# ledControlpcb.net
KiCad netlist of a schematic drawn in EAGLE
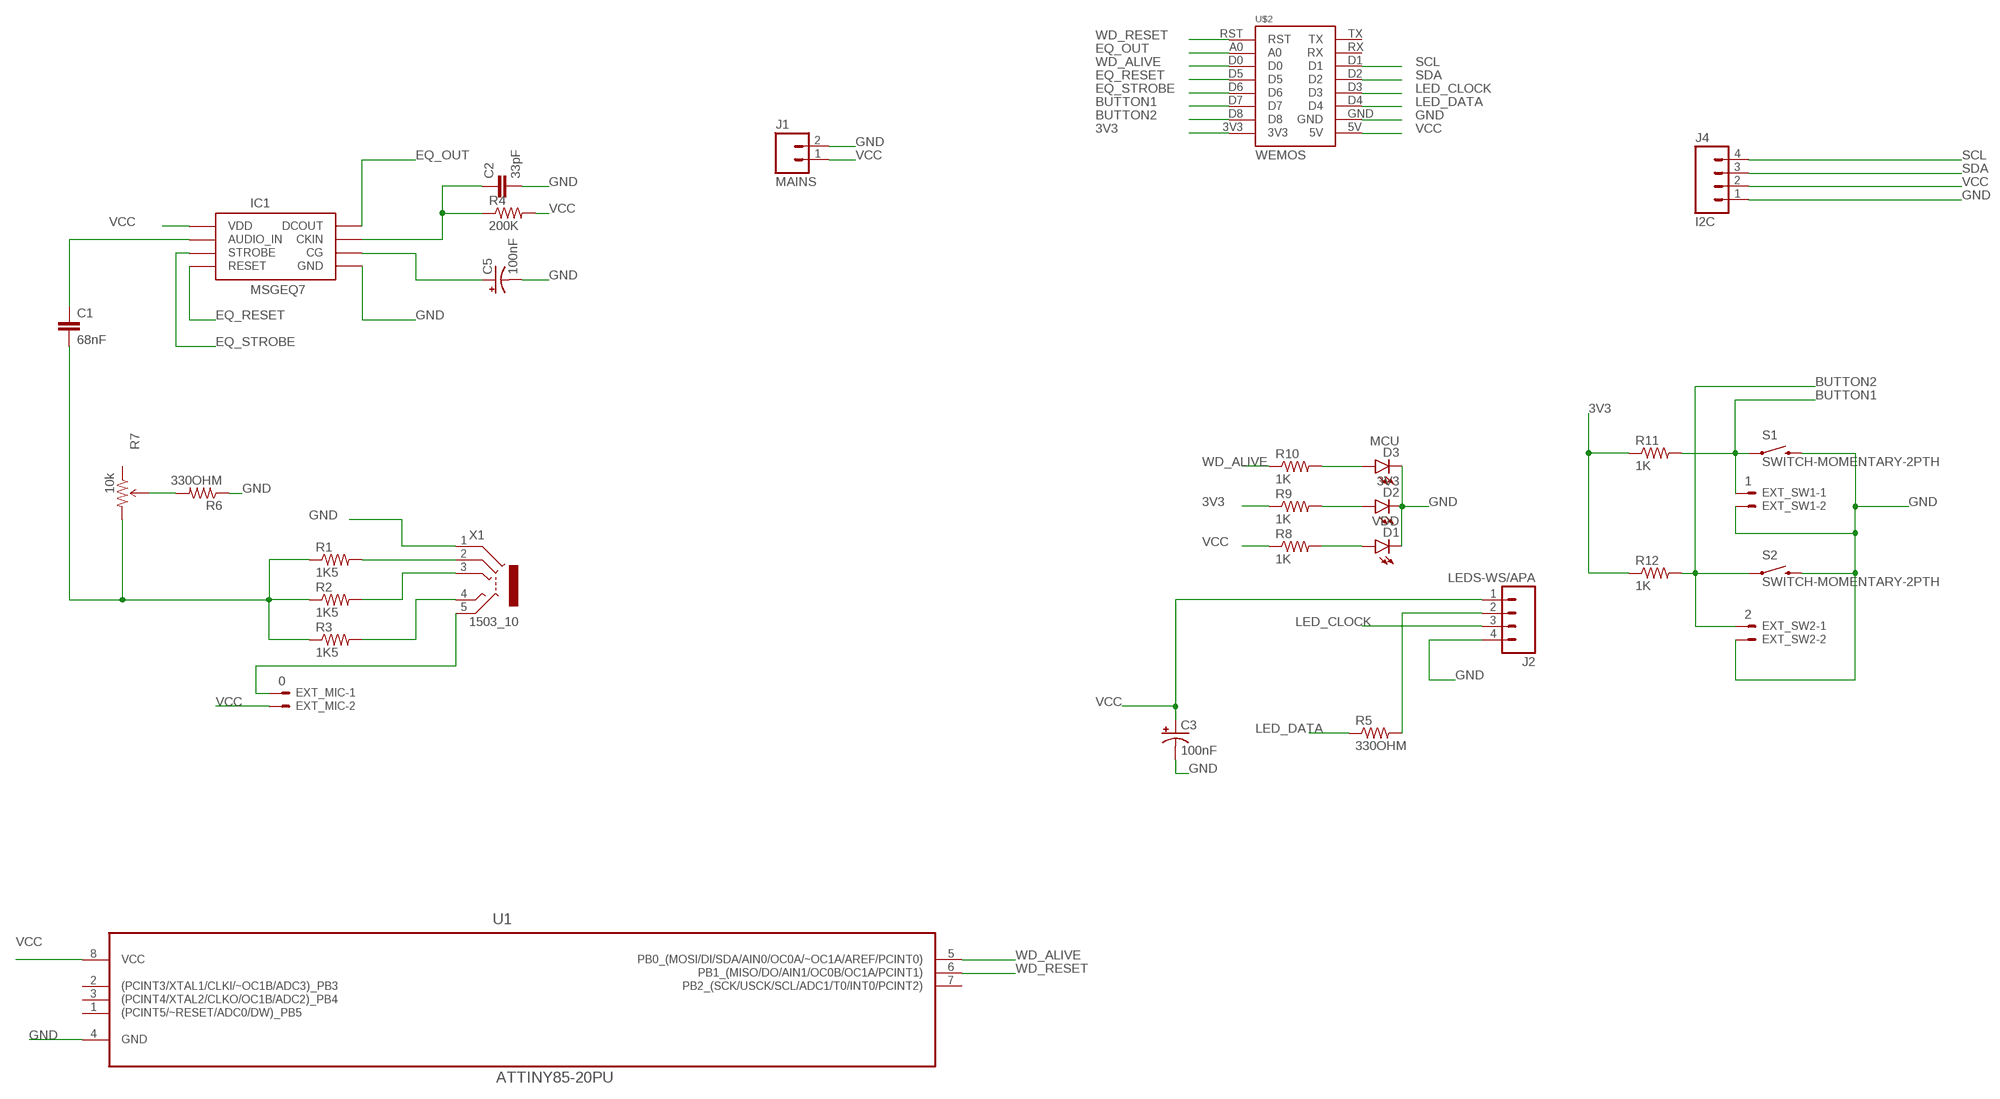
[diagram p0: schematic, sheet 1]

(export (version "E")
  (design (tool "Eeschema 10.0.6"))
  (components
    (comp (ref "C1")
      (value "68nF")
      (footprint "eagle-import:0603-CAP")
      (libsource (lib "eagle-import") (part "CAP0603-CAP"))
    )
    (comp (ref "C2")
      (value "33pF")
      (footprint "eagle-import:0603-CAP")
      (libsource (lib "eagle-import") (part "CAP0603-CAP"))
    )
    (comp (ref "C3")
      (value "100nF")
      (footprint "eagle-import:EIA3216")
      (libsource (lib "eagle-import") (part "CAP_POL1206"))
    )
    (comp (ref "C5")
      (value "100nF")
      (footprint "eagle-import:EIA3216")
      (libsource (lib "eagle-import") (part "CAP_POL1206"))
    )
    (comp (ref "D1")
      (value "VDD")
      (footprint "eagle-import:LED-0603")
      (libsource (lib "eagle-import") (part "LED0603"))
    )
    (comp (ref "D2")
      (value "3V3")
      (footprint "eagle-import:LED-0603")
      (libsource (lib "eagle-import") (part "LED0603"))
    )
    (comp (ref "D3")
      (value "MCU")
      (footprint "eagle-import:LED-0603")
      (libsource (lib "eagle-import") (part "LED0603"))
    )
    (comp (ref "EXT_MIC")
      (value "0")
      (footprint "eagle-import:22-23-2021")
      (fields (field (name "MF") "MOLEX") (field (name "MPN") "22-23-2021"))
      (libsource (lib "eagle-import") (part "22-23-2021"))
    )
    (comp (ref "EXT_SW1")
      (value "1")
      (footprint "eagle-import:22-23-2021")
      (fields (field (name "MF") "MOLEX") (field (name "MPN") "22-23-2021"))
      (libsource (lib "eagle-import") (part "22-23-2021"))
    )
    (comp (ref "EXT_SW2")
      (value "2")
      (footprint "eagle-import:22-23-2021")
      (fields (field (name "MF") "MOLEX") (field (name "MPN") "22-23-2021"))
      (libsource (lib "eagle-import") (part "22-23-2021"))
    )
    (comp (ref "IC1")
      (value "MSGEQ7DIP")
      (footprint "eagle-import:DIL08")
      (libsource (lib "eagle-import") (part "MSGEQ7DIP"))
    )
    (comp (ref "J1")
      (value "MAINS")
      (footprint "eagle-import:MOLEX-1X2")
      (libsource (lib "eagle-import") (part "M02POLAR"))
    )
    (comp (ref "J2")
      (value "LEDS-WS/APA")
      (footprint "eagle-import:MOLEX-1X4")
      (libsource (lib "eagle-import") (part "M04POLAR"))
    )
    (comp (ref "J4")
      (value "I2C")
      (footprint "eagle-import:MOLEX-1X4")
      (libsource (lib "eagle-import") (part "M04POLAR"))
    )
    (comp (ref "R1")
      (value "1K5")
      (footprint "eagle-import:0603-RES")
      (libsource (lib "eagle-import") (part "RESISTOR0603"))
    )
    (comp (ref "R2")
      (value "1K5")
      (footprint "eagle-import:0603-RES")
      (libsource (lib "eagle-import") (part "RESISTOR0603"))
    )
    (comp (ref "R3")
      (value "1K5")
      (footprint "eagle-import:0603-RES")
      (libsource (lib "eagle-import") (part "RESISTOR0603-RES"))
    )
    (comp (ref "R4")
      (value "200K")
      (footprint "eagle-import:0603-RES")
      (libsource (lib "eagle-import") (part "RESISTOR0603"))
    )
    (comp (ref "R5")
      (value "330OHM")
      (footprint "eagle-import:0603-RES")
      (libsource (lib "eagle-import") (part "RESISTOR0603"))
    )
    (comp (ref "R6")
      (value "330OHM")
      (footprint "eagle-import:0603-RES")
      (libsource (lib "eagle-import") (part "RESISTOR0603-RES"))
    )
    (comp (ref "R7")
      (value "10k")
      (footprint "eagle-import:TRIM_POT_PTH")
      (libsource (lib "eagle-import") (part "TRIMPOTPTH"))
    )
    (comp (ref "R8")
      (value "1K")
      (footprint "eagle-import:0603-RES")
      (libsource (lib "eagle-import") (part "RESISTOR0603"))
    )
    (comp (ref "R9")
      (value "1K")
      (footprint "eagle-import:0603-RES")
      (libsource (lib "eagle-import") (part "RESISTOR0603"))
    )
    (comp (ref "R10")
      (value "1K")
      (footprint "eagle-import:0603-RES")
      (libsource (lib "eagle-import") (part "RESISTOR0603"))
    )
    (comp (ref "R11")
      (value "1K")
      (footprint "eagle-import:0603-RES")
      (libsource (lib "eagle-import") (part "RESISTOR0603"))
    )
    (comp (ref "R12")
      (value "1K")
      (footprint "eagle-import:0603-RES")
      (libsource (lib "eagle-import") (part "RESISTOR0603"))
    )
    (comp (ref "S1")
      (value "SWITCH-MOMENTARY-2PTH")
      (footprint "eagle-import:TACTILE-PTH")
      (libsource (lib "eagle-import") (part "SWITCH-MOMENTARY-2PTH"))
    )
    (comp (ref "S2")
      (value "SWITCH-MOMENTARY-2PTH")
      (footprint "eagle-import:TACTILE-PTH")
      (libsource (lib "eagle-import") (part "SWITCH-MOMENTARY-2PTH"))
    )
    (comp (ref "U$2")
      (value "WEMOS")
      (footprint "eagle-import:WEMOS")
      (libsource (lib "eagle-import") (part "WEMOS"))
    )
    (comp (ref "U1")
      (value "ATTINY85-20PU")
      (footprint "eagle-import:DIP254P762X533-8")
      (libsource (lib "eagle-import") (part "ATTINY85-20PU"))
    )
    (comp (ref "X1")
      (value "1503_10")
      (footprint "eagle-import:1503_10")
      (libsource (lib "eagle-import") (part "1503_10"))
    )
  )
  (nets
    (net (code "1") (name "/3V3") (class "Default")
      (node (ref "R11") (pin "1") (pinfunction "1_1") (pintype "passive"))
      (node (ref "R12") (pin "1") (pinfunction "1_1") (pintype "passive"))
      (node (ref "R9") (pin "1") (pinfunction "1_1") (pintype "passive"))
      (node (ref "U$2") (pin "3V3") (pinfunction "3V3_3V3") (pintype "bidirectional"))
    )
    (net (code "2") (name "/BUTTON1") (class "Default")
      (node (ref "EXT_SW1") (pin "1") (pinfunction "S_1") (pintype "passive"))
      (node (ref "R11") (pin "2") (pinfunction "2_2") (pintype "passive"))
      (node (ref "S1") (pin "1") (pinfunction "1_1") (pintype "passive"))
      (node (ref "U$2") (pin "D7") (pinfunction "D7_D7") (pintype "bidirectional"))
    )
    (net (code "3") (name "/BUTTON2") (class "Default")
      (node (ref "EXT_SW2") (pin "1") (pinfunction "S_1") (pintype "passive"))
      (node (ref "R12") (pin "2") (pinfunction "2_2") (pintype "passive"))
      (node (ref "S2") (pin "1") (pinfunction "1_1") (pintype "passive"))
      (node (ref "U$2") (pin "D8") (pinfunction "D8_D8") (pintype "bidirectional"))
    )
    (net (code "4") (name "/EQ_OUT") (class "Default")
      (node (ref "IC1") (pin "3") (pinfunction "DCOUT_3") (pintype "bidirectional"))
      (node (ref "U$2") (pin "A0") (pinfunction "A0_A0") (pintype "bidirectional"))
    )
    (net (code "5") (name "/EQ_RESET") (class "Default")
      (node (ref "IC1") (pin "7") (pinfunction "RESET_7") (pintype "input"))
      (node (ref "U$2") (pin "D5") (pinfunction "D5_D5") (pintype "bidirectional"))
    )
    (net (code "6") (name "/EQ_STROBE") (class "Default")
      (node (ref "IC1") (pin "4") (pinfunction "STROBE_4") (pintype "input"))
      (node (ref "U$2") (pin "D6") (pinfunction "D6_D6") (pintype "bidirectional"))
    )
    (net (code "7") (name "/GND") (class "Default")
      (node (ref "C2") (pin "2") (pinfunction "2_2") (pintype "passive"))
      (node (ref "C3") (pin "C") (pinfunction "-_C") (pintype "passive"))
      (node (ref "C5") (pin "C") (pinfunction "-_C") (pintype "passive"))
      (node (ref "D1") (pin "C") (pinfunction "C_C") (pintype "passive"))
      (node (ref "D2") (pin "C") (pinfunction "C_C") (pintype "passive"))
      (node (ref "D3") (pin "C") (pinfunction "C_C") (pintype "passive"))
      (node (ref "EXT_SW1") (pin "2") (pinfunction "S_2") (pintype "passive"))
      (node (ref "EXT_SW2") (pin "2") (pinfunction "S_2") (pintype "passive"))
      (node (ref "IC1") (pin "2") (pinfunction "GND_2") (pintype "bidirectional"))
      (node (ref "J1") (pin "2") (pinfunction "2_2") (pintype "passive"))
      (node (ref "J2") (pin "4") (pinfunction "4_4") (pintype "passive"))
      (node (ref "J4") (pin "1") (pinfunction "1_1") (pintype "passive"))
      (node (ref "R6") (pin "1") (pinfunction "1_1") (pintype "passive"))
      (node (ref "S1") (pin "3") (pinfunction "2_3") (pintype "passive"))
      (node (ref "S2") (pin "3") (pinfunction "2_3") (pintype "passive"))
      (node (ref "U$2") (pin "GND") (pinfunction "GND_GND") (pintype "bidirectional"))
      (node (ref "U1") (pin "4") (pinfunction "GND_4") (pintype "passive"))
      (node (ref "X1") (pin "1") (pinfunction "1_1") (pintype "passive"))
    )
    (net (code "8") (name "/LED_CLOCK") (class "Default")
      (node (ref "J2") (pin "3") (pinfunction "3_3") (pintype "passive"))
      (node (ref "U$2") (pin "D3") (pinfunction "D3_D3") (pintype "bidirectional"))
    )
    (net (code "9") (name "/LED_DATA") (class "Default")
      (node (ref "R5") (pin "1") (pinfunction "1_1") (pintype "passive"))
      (node (ref "U$2") (pin "D4") (pinfunction "D4_D4") (pintype "bidirectional"))
    )
    (net (code "10") (name "/SCL") (class "Default")
      (node (ref "J4") (pin "4") (pinfunction "4_4") (pintype "passive"))
      (node (ref "U$2") (pin "D1") (pinfunction "D1_D1") (pintype "bidirectional"))
    )
    (net (code "11") (name "/SDA") (class "Default")
      (node (ref "J4") (pin "3") (pinfunction "3_3") (pintype "passive"))
      (node (ref "U$2") (pin "D2") (pinfunction "D2_D2") (pintype "bidirectional"))
    )
    (net (code "12") (name "/VCC") (class "Default")
      (node (ref "C3") (pin "A") (pinfunction "+_A") (pintype "passive"))
      (node (ref "EXT_MIC") (pin "2") (pinfunction "S_2") (pintype "passive"))
      (node (ref "IC1") (pin "1") (pinfunction "VDD_1") (pintype "input"))
      (node (ref "J1") (pin "1") (pinfunction "1_1") (pintype "passive"))
      (node (ref "J2") (pin "1") (pinfunction "1_1") (pintype "passive"))
      (node (ref "J4") (pin "2") (pinfunction "2_2") (pintype "passive"))
      (node (ref "R4") (pin "2") (pinfunction "2_2") (pintype "passive"))
      (node (ref "R8") (pin "1") (pinfunction "1_1") (pintype "passive"))
      (node (ref "U$2") (pin "5V") (pinfunction "5V_5V") (pintype "bidirectional"))
      (node (ref "U1") (pin "8") (pinfunction "VCC_8") (pintype "power_in"))
    )
    (net (code "13") (name "/WD_ALIVE") (class "Default")
      (node (ref "R10") (pin "1") (pinfunction "1_1") (pintype "passive"))
      (node (ref "U$2") (pin "D0") (pinfunction "D0_D0") (pintype "bidirectional"))
      (node (ref "U1") (pin "5") (pinfunction "PB0_(MOSI/DI/SDA/AIN0/OC0A/~{OC1A/AREF/PCINT0})_5") (pintype "bidirectional"))
    )
    (net (code "14") (name "/WD_RESET") (class "Default")
      (node (ref "U$2") (pin "RST") (pinfunction "RST_RST") (pintype "bidirectional"))
      (node (ref "U1") (pin "6") (pinfunction "PB1_(MISO/DO/AIN1/OC0B/OC1A/PCINT1)_6") (pintype "bidirectional"))
    )
    (net (code "15") (name "Net-(C5-+)") (class "Default")
      (node (ref "C5") (pin "A") (pinfunction "+_A") (pintype "passive"))
      (node (ref "IC1") (pin "6") (pinfunction "CG_6") (pintype "bidirectional"))
    )
    (net (code "16") (name "Net-(D1-PadA)") (class "Default")
      (node (ref "D1") (pin "A") (pinfunction "A_A") (pintype "passive"))
      (node (ref "R8") (pin "2") (pinfunction "2_2") (pintype "passive"))
    )
    (net (code "17") (name "Net-(D2-PadA)") (class "Default")
      (node (ref "D2") (pin "A") (pinfunction "A_A") (pintype "passive"))
      (node (ref "R9") (pin "2") (pinfunction "2_2") (pintype "passive"))
    )
    (net (code "18") (name "Net-(D3-PadA)") (class "Default")
      (node (ref "D3") (pin "A") (pinfunction "A_A") (pintype "passive"))
      (node (ref "R10") (pin "2") (pinfunction "2_2") (pintype "passive"))
    )
    (net (code "19") (name "Net-(EXT_MICA-S)") (class "Default")
      (node (ref "EXT_MIC") (pin "1") (pinfunction "S_1") (pintype "passive"))
      (node (ref "X1") (pin "5") (pinfunction "5_5") (pintype "passive"))
    )
    (net (code "20") (name "Net-(IC1-AUDIO_IN)") (class "Default")
      (node (ref "C1") (pin "1") (pinfunction "1_1") (pintype "passive"))
      (node (ref "IC1") (pin "5") (pinfunction "AUDIO_IN_5") (pintype "input"))
    )
    (net (code "21") (name "Net-(IC1-CKIN)") (class "Default")
      (node (ref "C2") (pin "1") (pinfunction "1_1") (pintype "passive"))
      (node (ref "IC1") (pin "8") (pinfunction "CKIN_8") (pintype "bidirectional"))
      (node (ref "R4") (pin "1") (pinfunction "1_1") (pintype "passive"))
    )
    (net (code "22") (name "Net-(J2-Pad2)") (class "Default")
      (node (ref "J2") (pin "2") (pinfunction "2_2") (pintype "passive"))
      (node (ref "R5") (pin "2") (pinfunction "2_2") (pintype "passive"))
    )
    (net (code "23") (name "Net-(R1-Pad2)") (class "Default")
      (node (ref "R1") (pin "2") (pinfunction "2_2") (pintype "passive"))
      (node (ref "X1") (pin "2") (pinfunction "2_2") (pintype "passive"))
    )
    (net (code "24") (name "Net-(R2-Pad2)") (class "Default")
      (node (ref "R2") (pin "2") (pinfunction "2_2") (pintype "passive"))
      (node (ref "X1") (pin "3") (pinfunction "3_3") (pintype "passive"))
    )
    (net (code "25") (name "Net-(R3-Pad2)") (class "Default")
      (node (ref "R3") (pin "2") (pinfunction "2_2") (pintype "passive"))
      (node (ref "X1") (pin "4") (pinfunction "4_4") (pintype "passive"))
    )
    (net (code "26") (name "Net-(R7-CW)") (class "Default")
      (node (ref "C1") (pin "2") (pinfunction "2_2") (pintype "passive"))
      (node (ref "R1") (pin "1") (pinfunction "1_1") (pintype "passive"))
      (node (ref "R2") (pin "1") (pinfunction "1_1") (pintype "passive"))
      (node (ref "R3") (pin "1") (pinfunction "1_1") (pintype "passive"))
      (node (ref "R7") (pin "3") (pinfunction "CW_3") (pintype "passive"))
    )
    (net (code "27") (name "Net-(R7-WIPER)") (class "Default")
      (node (ref "R6") (pin "2") (pinfunction "2_2") (pintype "passive"))
      (node (ref "R7") (pin "2") (pinfunction "WIPER_2") (pintype "passive"))
    )
    (net (code "28") (name "unconnected-(R7-CCW-Pad1)") (class "Default")
      (node (ref "R7") (pin "1") (pinfunction "CCW_1") (pintype "passive"))
    )
    (net (code "29") (name "unconnected-(U$2-PadRX)") (class "Default")
      (node (ref "U$2") (pin "RX") (pinfunction "RX_RX") (pintype "bidirectional"))
    )
    (net (code "30") (name "unconnected-(U$2-PadTX)") (class "Default")
      (node (ref "U$2") (pin "TX") (pinfunction "TX_TX") (pintype "bidirectional"))
    )
    (net (code "31") (name "unconnected-(U1-(PCINT3{slash}XTAL1{slash}CLKI{slash}~{OC1B{slash}ADC3})_PB3-Pad2)") (class "Default")
      (node (ref "U1") (pin "2") (pinfunction "(PCINT3/XTAL1/CLKI/~{OC1B/ADC3})_PB3_2") (pintype "bidirectional"))
    )
    (net (code "32") (name "unconnected-(U1-(PCINT4{slash}XTAL2{slash}CLKO{slash}OC1B{slash}ADC2)_PB4-Pad3)") (class "Default")
      (node (ref "U1") (pin "3") (pinfunction "(PCINT4/XTAL2/CLKO/OC1B/ADC2)_PB4_3") (pintype "bidirectional"))
    )
    (net (code "33") (name "unconnected-(U1-(PCINT5{slash}~{RESET{slash}ADC0{slash}DW})_PB5-Pad1)") (class "Default")
      (node (ref "U1") (pin "1") (pinfunction "(PCINT5/~{RESET/ADC0/DW})_PB5_1") (pintype "bidirectional"))
    )
    (net (code "34") (name "unconnected-(U1-PB2_(SCK{slash}USCK{slash}SCL{slash}ADC1{slash}T0{slash}INT0{slash}PCINT2)-Pad7)") (class "Default")
      (node (ref "U1") (pin "7") (pinfunction "PB2_(SCK/USCK/SCL/ADC1/T0/INT0/PCINT2)_7") (pintype "bidirectional"))
    )
  )
)
